# FPGA_USB.net
KiCad netlist of a schematic drawn in Altium Designer
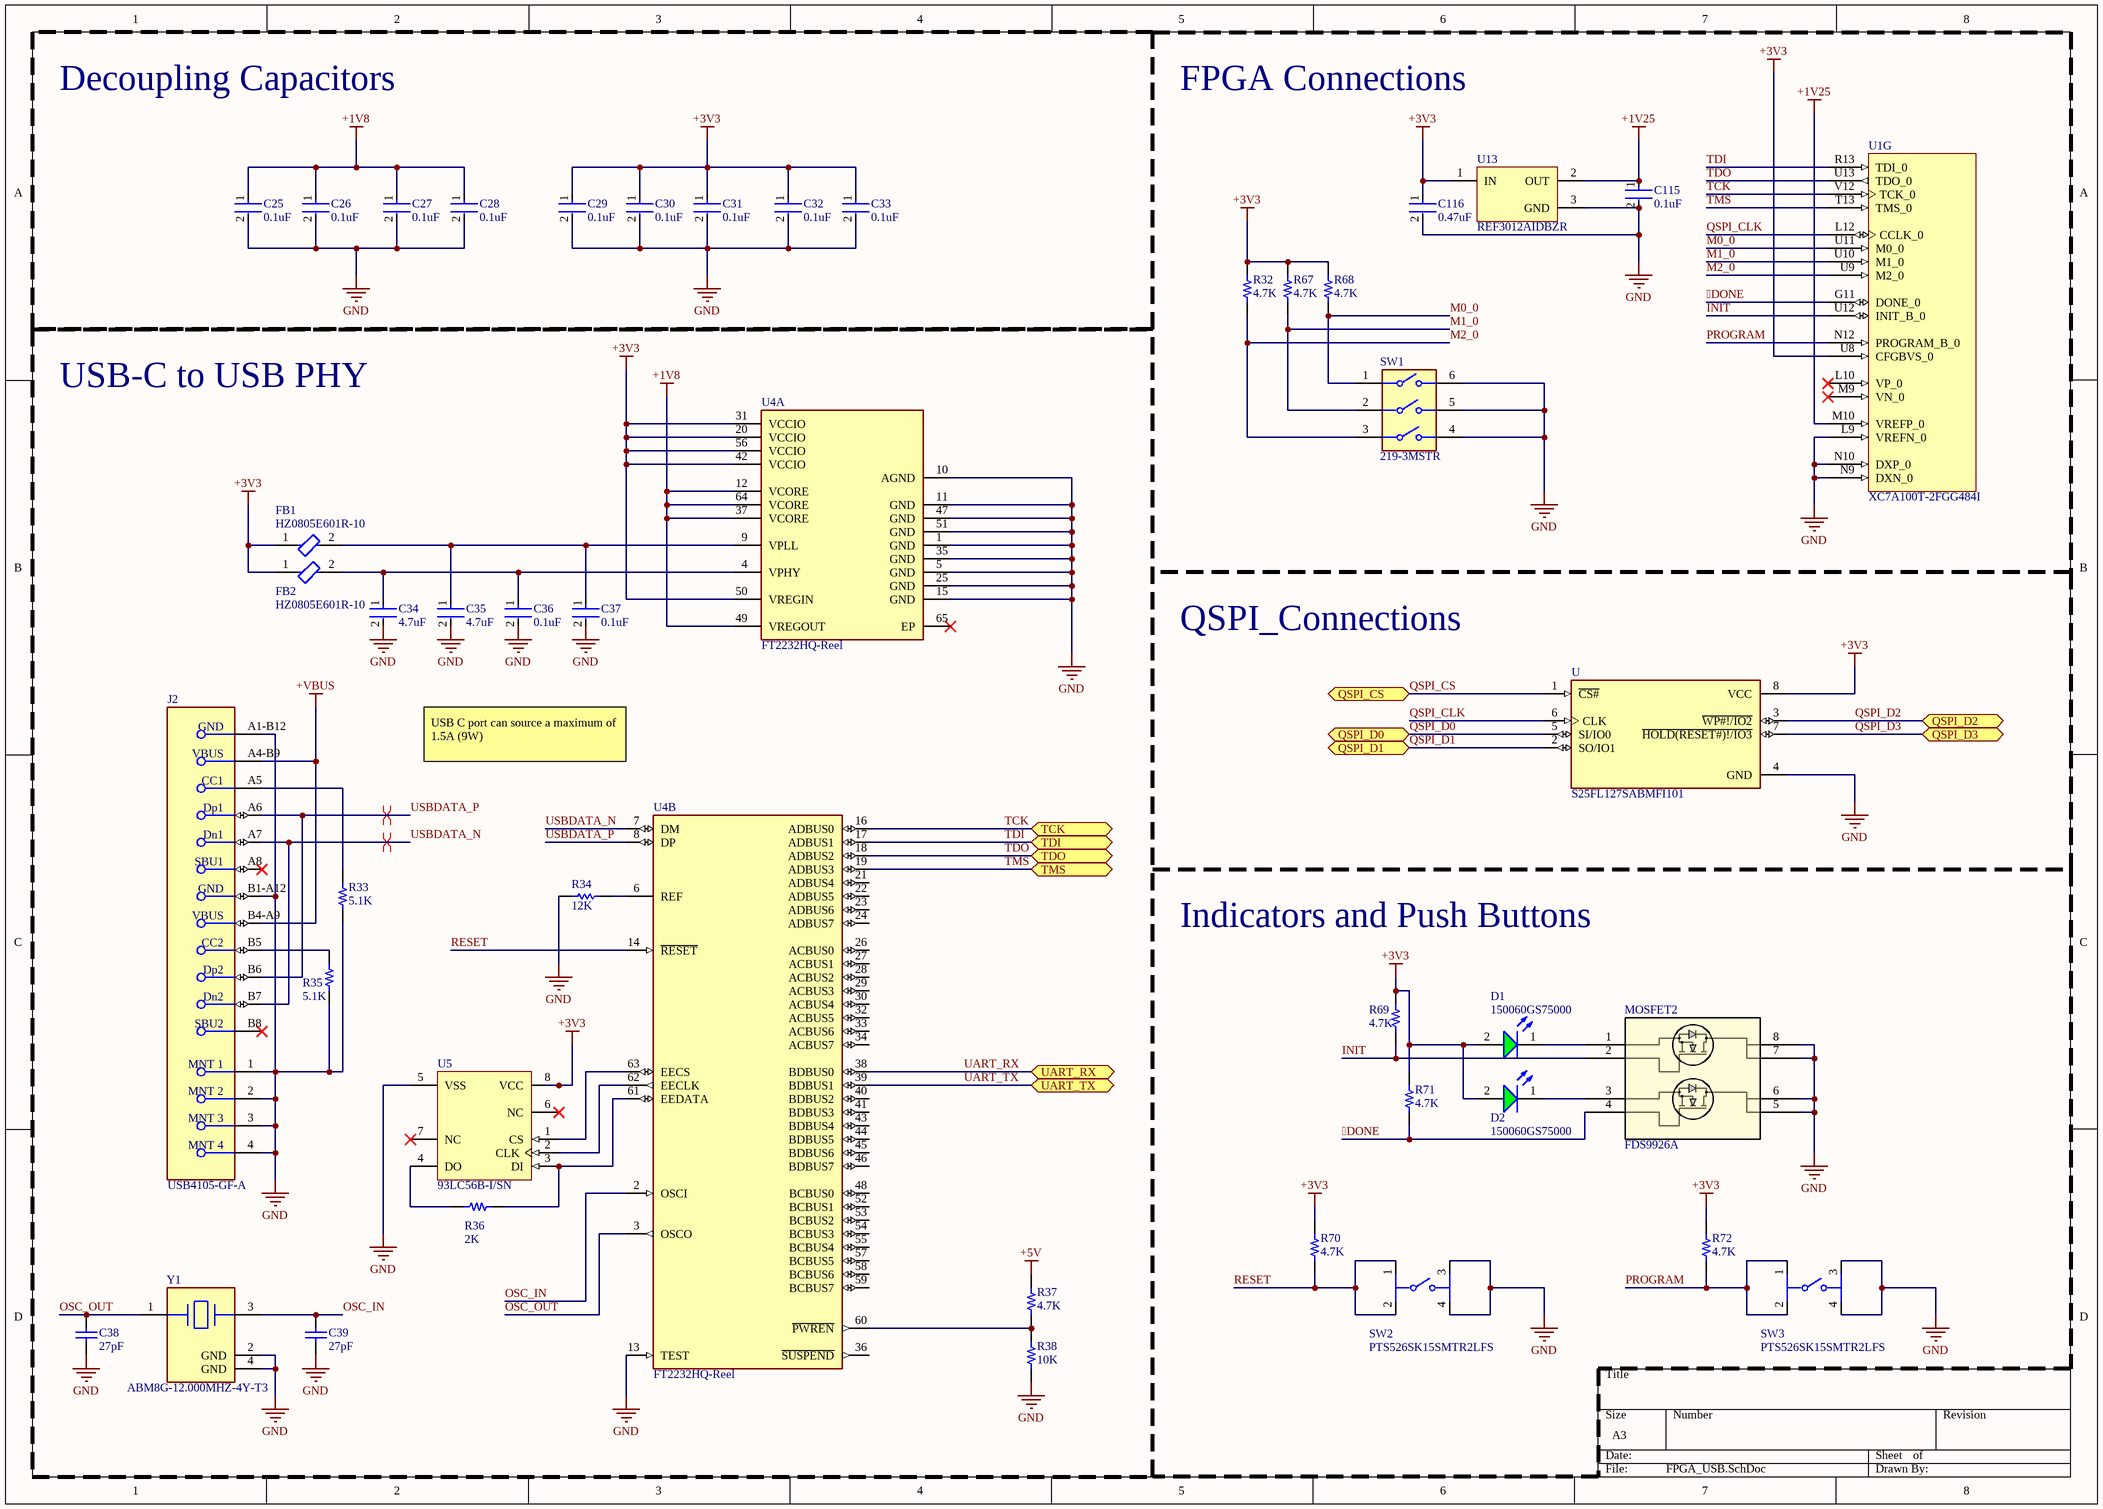
[diagram p0: FPGA_USB.SchDoc]

(export (version "E")
  (design (tool "Eeschema 10.0.6"))
  (components
    (comp (ref "C25")
      (value "0.1uF")
      (footprint "FP-CC0402-MFG")
      (description "CAP CER 0.1UF 16V X7R 0402")
      (fields (field (name "MANUFACTURER") "YAGEO") (field (name "TOLERANCE") "0.1"))
      (libsource (lib "Altium Content Vault") (part "11868f565c42a9108669ba33697ecf6"))
    )
    (comp (ref "C26")
      (value "0.1uF")
      (footprint "FP-CC0402-MFG")
      (description "CAP CER 0.1UF 16V X7R 0402")
      (fields (field (name "MANUFACTURER") "YAGEO") (field (name "TOLERANCE") "0.1"))
      (libsource (lib "Altium Content Vault") (part "11868f565c42a9108669ba33697ecf6"))
    )
    (comp (ref "C27")
      (value "0.1uF")
      (footprint "FP-CC0402-MFG")
      (description "CAP CER 0.1UF 16V X7R 0402")
      (fields (field (name "MANUFACTURER") "YAGEO") (field (name "TOLERANCE") "0.1"))
      (libsource (lib "Altium Content Vault") (part "11868f565c42a9108669ba33697ecf6"))
    )
    (comp (ref "C28")
      (value "0.1uF")
      (footprint "FP-CC0402-MFG")
      (description "CAP CER 0.1UF 16V X7R 0402")
      (fields (field (name "MANUFACTURER") "YAGEO") (field (name "TOLERANCE") "0.1"))
      (libsource (lib "Altium Content Vault") (part "11868f565c42a9108669ba33697ecf6"))
    )
    (comp (ref "C29")
      (value "0.1uF")
      (footprint "FP-CC0402-MFG")
      (description "CAP CER 0.1UF 16V X7R 0402")
      (fields (field (name "MANUFACTURER") "YAGEO") (field (name "TOLERANCE") "0.1"))
      (libsource (lib "Altium Content Vault") (part "11868f565c42a9108669ba33697ecf6"))
    )
    (comp (ref "C30")
      (value "0.1uF")
      (footprint "FP-CC0402-MFG")
      (description "CAP CER 0.1UF 16V X7R 0402")
      (fields (field (name "MANUFACTURER") "YAGEO") (field (name "TOLERANCE") "0.1"))
      (libsource (lib "Altium Content Vault") (part "11868f565c42a9108669ba33697ecf6"))
    )
    (comp (ref "C31")
      (value "0.1uF")
      (footprint "FP-CC0402-MFG")
      (description "CAP CER 0.1UF 16V X7R 0402")
      (fields (field (name "MANUFACTURER") "YAGEO") (field (name "TOLERANCE") "0.1"))
      (libsource (lib "Altium Content Vault") (part "11868f565c42a9108669ba33697ecf6"))
    )
    (comp (ref "C32")
      (value "0.1uF")
      (footprint "FP-CC0402-MFG")
      (description "CAP CER 0.1UF 16V X7R 0402")
      (fields (field (name "MANUFACTURER") "YAGEO") (field (name "TOLERANCE") "0.1"))
      (libsource (lib "Altium Content Vault") (part "11868f565c42a9108669ba33697ecf6"))
    )
    (comp (ref "C33")
      (value "0.1uF")
      (footprint "FP-CC0402-MFG")
      (description "CAP CER 0.1UF 16V X7R 0402")
      (fields (field (name "MANUFACTURER") "YAGEO") (field (name "TOLERANCE") "0.1"))
      (libsource (lib "Altium Content Vault") (part "11868f565c42a9108669ba33697ecf6"))
    )
    (comp (ref "C34")
      (value "4.7uF")
      (footprint "FP-CC0402-MFG")
      (description "CAP CER 4.7UF 10V X5R 0402")
      (fields
        (field (name "MANUFACTURER PART NUMBER") "CC0402MRX5R6BB475")
        (field (name "OCTOPART") "https://octopart.com/cc0402mrx5r6bb475-yageo-57080755")
      )
      (libsource (lib "Altium Content Vault") (part "11868f565c42a9108669ba33697ecf6"))
    )
    (comp (ref "C35")
      (value "4.7uF")
      (footprint "FP-CC0402-MFG")
      (description "CAP CER 4.7UF 10V X5R 0402")
      (fields
        (field (name "MANUFACTURER PART NUMBER") "CC0402MRX5R6BB475")
        (field (name "OCTOPART") "https://octopart.com/cc0402mrx5r6bb475-yageo-57080755")
      )
      (libsource (lib "Altium Content Vault") (part "11868f565c42a9108669ba33697ecf6"))
    )
    (comp (ref "C36")
      (value "0.1uF")
      (footprint "FP-CC0402-MFG")
      (description "CAP CER 0.1UF 16V X7R 0402")
      (fields (field (name "MANUFACTURER") "YAGEO") (field (name "TOLERANCE") "0.1"))
      (libsource (lib "Altium Content Vault") (part "11868f565c42a9108669ba33697ecf6"))
    )
    (comp (ref "C37")
      (value "0.1uF")
      (footprint "FP-CC0402-MFG")
      (description "CAP CER 0.1UF 16V X7R 0402")
      (fields (field (name "MANUFACTURER") "YAGEO") (field (name "TOLERANCE") "0.1"))
      (libsource (lib "Altium Content Vault") (part "11868f565c42a9108669ba33697ecf6"))
    )
    (comp (ref "C38")
      (value "27pF")
      (footprint "CAPC1005X55X25LL05T10")
      (fields (field (name "PART NUMBER") "GRM1555C1H270JA01D") (field (name "MANUFACTURER") "Murata"))
      (libsource (lib "Altium Content Vault") (part "CAP"))
    )
    (comp (ref "C39")
      (value "27pF")
      (footprint "CAPC1005X55X25LL05T10")
      (fields (field (name "PART NUMBER") "GRM1555C1H270JA01D") (field (name "MANUFACTURER") "Murata"))
      (libsource (lib "Altium Content Vault") (part "CAP"))
    )
    (comp (ref "C115")
      (value "0.1uF")
      (footprint "FP-CC0402-MFG")
      (description "CAP CER 0.1UF 16V X7R 0402")
      (fields (field (name "MANUFACTURER") "YAGEO") (field (name "TOLERANCE") "0.1"))
      (libsource (lib "Altium Content Vault") (part "11868f565c42a9108669ba33697ecf6"))
    )
    (comp (ref "C116")
      (value "0.47uF")
      (footprint "FP-GRM188-0_1-e0_2_0_5-MFG")
      (description "Chip Multilayer Ceramic Capacitors for General Purpose, 0603, 0.47uF, X7R, 15%, 10%, 25V")
      (fields (field (name "TOLERANCE") "10%") (field (name "VOLTAGE") "50V"))
      (libsource (lib "Altium Content Vault") (part "11868f565c42a9108669ba33697ecf6"))
    )
    (comp (ref "D1")
      (value "150060GS75000")
      (footprint "WL-SMCW_0603_150060xx75000")
      (libsource (lib "Altium Content Vault") (part "LED_Green_2A-1K"))
    )
    (comp (ref "D2")
      (value "150060GS75000")
      (footprint "WL-SMCW_0603_150060xx75000")
      (libsource (lib "Altium Content Vault") (part "LED_Green_2A-1K"))
    )
    (comp (ref "FB1")
      (value "HZ0805E601R-10")
      (footprint "FP-HZ0805-MFG")
      (description "FERRITE BEAD 600 OHM 0805 1LN")
      (libsource (lib "Altium Content Vault") (part "5f30dd21d616792df468990f7003faa"))
    )
    (comp (ref "FB2")
      (value "HZ0805E601R-10")
      (footprint "FP-HZ0805-MFG")
      (description "FERRITE BEAD 600 OHM 0805 1LN")
      (libsource (lib "Altium Content Vault") (part "5f30dd21d616792df468990f7003faa"))
    )
    (comp (ref "J2")
      (value "USB4105-GF-A")
      (footprint "FP-USB4105-GF-A-MFG")
      (description "CONN RCPT USB2.0 TYPEC 5A")
      (fields
        (field (name "MANUFACTURER") "GCT")
        (field (name "OCTOPART") "https://octopart.com/usb4105-gf-a-gct-106627878")
      )
      (libsource (lib "Altium Content Vault") (part "e7c17a616881a82b79941196b4bec10"))
    )
    (comp (ref "MOSFET2")
      (value "FDS9926A")
      (footprint "SOIC8_751EB_ONS-M")
      (description "No Description Available")
      (libsource (lib "BIG_FPGA") (part "FDS9926A"))
    )
    (comp (ref "R32")
      (value "4.7K")
      (footprint "RES 0603_1608")
      (libsource (lib "Midnight Sun") (part "Resistor"))
    )
    (comp (ref "R33")
      (value "5.1K")
      (footprint "RES 0603_1608")
      (description "5.1 kOhms ±1% 0.1W, 1/10W Chip Resistor 0603 (1608 Metric) Automotive AEC-Q200 Thick Film")
      (libsource (lib "Midnight Sun") (part "Resistor"))
    )
    (comp (ref "R34")
      (value "12K")
      (footprint "RESC1608X55X25NL10T15")
      (description "Chip Resistor, 12 KOhm, +/- 1%, 100 mW, -55 to 155 degC, 0603 (1608 Metric), RoHS, Tape and Reel")
      (fields (field (name "TOLERANCE") "1%"))
      (libsource (lib "Altium Content Vault") (part "RES-2"))
    )
    (comp (ref "R35")
      (value "5.1K")
      (footprint "RES 0603_1608")
      (description "5.1 kOhms ±1% 0.1W, 1/10W Chip Resistor 0603 (1608 Metric) Automotive AEC-Q200 Thick Film")
      (libsource (lib "Midnight Sun") (part "Resistor"))
    )
    (comp (ref "R36")
      (value "2K")
      (footprint "RES 0603_1608")
      (description "2k Ohm ±1% 0.1W, 1/10W Chip Resistor 0603 (1608 Metric) Moisture Resistant Thick Film")
      (libsource (lib "Midnight Sun") (part "Resistor"))
    )
    (comp (ref "R37")
      (value "4.7K")
      (footprint "RES 0603_1608")
      (libsource (lib "Midnight Sun") (part "Resistor"))
    )
    (comp (ref "R38")
      (value "10K")
      (footprint "RES 0603_1608")
      (description "10 ±1% 0.1W, 1/10W Chip Resistor 0603 (1608 Metric) Automotive AEC-Q200 Thick Film")
      (libsource (lib "Midnight Sun") (part "Resistor"))
    )
    (comp (ref "R67")
      (value "4.7K")
      (footprint "RES 0603_1608")
      (libsource (lib "Midnight Sun") (part "Resistor"))
    )
    (comp (ref "R68")
      (value "4.7K")
      (footprint "RES 0603_1608")
      (libsource (lib "Midnight Sun") (part "Resistor"))
    )
    (comp (ref "R69")
      (value "4.7K")
      (footprint "RES 0603_1608")
      (libsource (lib "Midnight Sun") (part "Resistor"))
    )
    (comp (ref "R70")
      (value "4.7K")
      (footprint "RES 0603_1608")
      (libsource (lib "Midnight Sun") (part "Resistor"))
    )
    (comp (ref "R71")
      (value "4.7K")
      (footprint "RES 0603_1608")
      (libsource (lib "Midnight Sun") (part "Resistor"))
    )
    (comp (ref "R72")
      (value "4.7K")
      (footprint "RES 0603_1608")
      (libsource (lib "Midnight Sun") (part "Resistor"))
    )
    (comp (ref "SW1")
      (value "219-3MSTR")
      (footprint "FP-219-3MSTR-MFG")
      (description "SWITCH SLIDE DIP SPST 100MA 20V")
      (libsource (lib "Altium Content Vault") (part "7c490946f25aa2bb1cd4cef5bc3ec4e"))
    )
    (comp (ref "SW2")
      (value "PTS526SK15SMTR2LFS")
      (footprint "FP-PTS526SK15SMTR2LFS-MFG")
      (description "TACT 5.2 X 5.2, 1.5 MM H, 260GF,")
      (fields
        (field (name "MANUFACTURER") "C&K")
        (field (name "OCTOPART") "https://octopart.com/pts526+sk15+smtr2+lfs-c%26k+components-100617999")
      )
      (libsource (lib "Altium Content Vault") (part "b8895f3f4cefb76e1819d2863dba89b"))
    )
    (comp (ref "SW3")
      (value "PTS526SK15SMTR2LFS")
      (footprint "FP-PTS526SK15SMTR2LFS-MFG")
      (description "TACT 5.2 X 5.2, 1.5 MM H, 260GF,")
      (fields
        (field (name "MANUFACTURER") "C&K")
        (field (name "OCTOPART") "https://octopart.com/pts526+sk15+smtr2+lfs-c%26k+components-100617999")
      )
      (libsource (lib "Altium Content Vault") (part "b8895f3f4cefb76e1819d2863dba89b"))
    )
    (comp (ref "U")
      (value "S25FL127SABMFI101")
      (footprint "SOIC127P800X216-8N")
      (description "FLASH - NOR Memory IC 128Mb _16M x 8_ SPI - Quad I/O 108MHz 8-SOIC")
      (fields
        (field (name "MF") "Cypress Semiconductor")
        (field (name "DIGI-KEY_PART_NUMBER") "1274-1045-ND")
      )
      (libsource (lib "BIG_FPGA") (part "S25FL127SABMFI101"))
    )
    (comp (ref "U1")
      (value "XC7A100T-2FGG484I")
      (footprint "FGG484")
      (description "Artix-7 FPGA, 285 User I/Os, 4 GTP, 484-Ball BGA, Speed Grade 2, Industrial Grade, Pb-Free")
      (fields (field (name "MANUFACTURER") "Xilinx") (field (name "GENERIC PART NUMBER") "XC7A100T"))
      (libsource (lib "Altium Content Vault") (part "XNLX-XC7A100T-XNLX-FGG484"))
    )
    (comp (ref "U4")
      (value "FT2232HQ-Reel")
      (footprint "FP-FT2232HQ-Reel-MFG")
      (description "USB Bridge, USB to UART,FIFO USB 2.0 UART Interface 64-QFN (9x9)")
      (fields (field (name "OCTOPART") "https://octopart.com/ft2232hq-reel-ftdi-19172126"))
      (libsource (lib "Altium Content Vault") (part "69ab9ac86b67af101dfdf5de5064102"))
    )
    (comp (ref "U5")
      (value "93LC56B-I/SN")
      (footprint "SOIC-SN8_L")
      (description "2K, 128x16-bit, 2.5V Microwire Serial EEPROM, 8-Pin SOIC 150mil, Industrial Temperature")
      (libsource (lib "Altium Content Vault") (part "MEM-SEEPROM-93AA46B-P-8"))
    )
    (comp (ref "U13")
      (value "REF3012AIDBZR")
      (footprint "DBZ0003A_M")
      (fields (field (name "MANUFACTURER") "Texas Instruments"))
      (libsource (lib "Altium Content Vault") (part "TI-REF3012DBZ3"))
    )
    (comp (ref "Y1")
      (value "ABM8G-12.000MHZ-4Y-T3")
      (footprint "FP-ABM8G-MFG")
      (description "Crystal 12MHz ±30ppm (Tol) ±30ppm (Stability) 10pF FUND 120Ω 4-Pin SMD T/R")
      (libsource (lib "Altium Content Vault") (part "48e526d86b7f2615d98721063c72f49"))
    )
  )
  (nets
    (net (code "1") (name "+1V8") (class "Default")
      (node (ref "C25") (pin "1") (pinfunction "1_1") (pintype "passive"))
      (node (ref "C26") (pin "1") (pinfunction "1_1") (pintype "passive"))
      (node (ref "C27") (pin "1") (pinfunction "1_1") (pintype "passive"))
      (node (ref "C28") (pin "1") (pinfunction "1_1") (pintype "passive"))
      (node (ref "U4") (pin "12") (pinfunction "VCORE_12") (pintype "power_in"))
      (node (ref "U4") (pin "37") (pinfunction "VCORE_37") (pintype "power_in"))
      (node (ref "U4") (pin "49") (pinfunction "VREGOUT_49") (pintype "power_in"))
      (node (ref "U4") (pin "64") (pinfunction "VCORE_64") (pintype "power_in"))
    )
    (net (code "2") (name "+1V25") (class "Default")
      (node (ref "C115") (pin "1") (pinfunction "1_1") (pintype "passive"))
      (node (ref "U1") (pin "M10") (pinfunction "VREFP_0_M10") (pintype "input"))
      (node (ref "U13") (pin "2") (pinfunction "OUT_2") (pintype "power_in"))
    )
    (net (code "3") (name "+3V3") (class "Default")
      (node (ref "C116") (pin "1") (pinfunction "1_1") (pintype "passive"))
      (node (ref "C29") (pin "1") (pinfunction "1_1") (pintype "passive"))
      (node (ref "C30") (pin "1") (pinfunction "1_1") (pintype "passive"))
      (node (ref "C31") (pin "1") (pinfunction "1_1") (pintype "passive"))
      (node (ref "C32") (pin "1") (pinfunction "1_1") (pintype "passive"))
      (node (ref "C33") (pin "1") (pinfunction "1_1") (pintype "passive"))
      (node (ref "D1") (pin "2") (pinfunction "A_2") (pintype "passive"))
      (node (ref "D2") (pin "2") (pinfunction "A_2") (pintype "passive"))
      (node (ref "FB1") (pin "1") (pinfunction "1_1") (pintype "passive"))
      (node (ref "FB2") (pin "1") (pinfunction "1_1") (pintype "passive"))
      (node (ref "R32") (pin "2") (pinfunction "2_2") (pintype "passive"))
      (node (ref "R67") (pin "1") (pinfunction "1_1") (pintype "passive"))
      (node (ref "R68") (pin "1") (pinfunction "1_1") (pintype "passive"))
      (node (ref "R69") (pin "1") (pinfunction "1_1") (pintype "passive"))
      (node (ref "R70") (pin "1") (pinfunction "1_1") (pintype "passive"))
      (node (ref "R71") (pin "1") (pinfunction "1_1") (pintype "passive"))
      (node (ref "R72") (pin "1") (pinfunction "1_1") (pintype "passive"))
      (node (ref "U") (pin "8") (pinfunction "VCC_8") (pintype "power_in"))
      (node (ref "U1") (pin "U8") (pinfunction "CFGBVS_0_U8") (pintype "input"))
      (node (ref "U13") (pin "1") (pinfunction "IN_1") (pintype "power_in"))
      (node (ref "U4") (pin "20") (pinfunction "VCCIO_20") (pintype "power_in"))
      (node (ref "U4") (pin "31") (pinfunction "VCCIO_31") (pintype "power_in"))
      (node (ref "U4") (pin "42") (pinfunction "VCCIO_42") (pintype "power_in"))
      (node (ref "U4") (pin "50") (pinfunction "VREGIN_50") (pintype "power_in"))
      (node (ref "U4") (pin "56") (pinfunction "VCCIO_56") (pintype "power_in"))
      (node (ref "U5") (pin "8") (pinfunction "VCC_8") (pintype "power_in"))
    )
    (net (code "4") (name "+5V") (class "Default")
      (node (ref "R37") (pin "1") (pinfunction "1_1") (pintype "passive"))
    )
    (net (code "5") (name "+VBUS") (class "Default")
      (node (ref "J2") (pin "A4-B9") (pinfunction "VBUS_A4-B9") (pintype "power_in"))
      (node (ref "J2") (pin "B4-A9") (pinfunction "VBUS_B4-A9") (pintype "bidirectional"))
    )
    (net (code "6") (name "/DONE") (class "Default")
      (node (ref "MOSFET2") (pin "4") (pinfunction "4_4") (pintype "passive"))
      (node (ref "R71") (pin "2") (pinfunction "2_2") (pintype "passive"))
      (node (ref "U1") (pin "G11") (pinfunction "DONE_0_G11") (pintype "bidirectional"))
    )
    (net (code "7") (name "/INIT") (class "Default")
      (node (ref "MOSFET2") (pin "2") (pinfunction "2_2") (pintype "passive"))
      (node (ref "R69") (pin "2") (pinfunction "2_2") (pintype "passive"))
      (node (ref "U1") (pin "U12") (pinfunction "INIT_B_0_U12") (pintype "bidirectional"))
    )
    (net (code "8") (name "/M0_0") (class "Default")
      (node (ref "R68") (pin "2") (pinfunction "2_2") (pintype "passive"))
      (node (ref "SW1") (pin "1") (pinfunction "1_1") (pintype "passive"))
      (node (ref "U1") (pin "U11") (pinfunction "M0_0_U11") (pintype "input"))
    )
    (net (code "9") (name "/M1_0") (class "Default")
      (node (ref "R67") (pin "2") (pinfunction "2_2") (pintype "passive"))
      (node (ref "SW1") (pin "2") (pinfunction "2_2") (pintype "passive"))
      (node (ref "U1") (pin "U10") (pinfunction "M1_0_U10") (pintype "input"))
    )
    (net (code "10") (name "/M2_0") (class "Default")
      (node (ref "R32") (pin "1") (pinfunction "1_1") (pintype "passive"))
      (node (ref "SW1") (pin "3") (pinfunction "3_3") (pintype "passive"))
      (node (ref "U1") (pin "U9") (pinfunction "M2_0_U9") (pintype "input"))
    )
    (net (code "11") (name "/OSC_IN") (class "Default")
      (node (ref "C39") (pin "1") (pinfunction "1_1") (pintype "passive"))
      (node (ref "U4") (pin "2") (pinfunction "OSCI_2") (pintype "input"))
      (node (ref "Y1") (pin "3") (pinfunction "3_3") (pintype "passive"))
    )
    (net (code "12") (name "/OSC_OUT") (class "Default")
      (node (ref "C38") (pin "1") (pinfunction "1_1") (pintype "passive"))
      (node (ref "U4") (pin "3") (pinfunction "OSCO_3") (pintype "output"))
      (node (ref "Y1") (pin "1") (pinfunction "1_1") (pintype "passive"))
    )
    (net (code "13") (name "/PROGRAM") (class "Default")
      (node (ref "R72") (pin "2") (pinfunction "2_2") (pintype "passive"))
      (node (ref "SW3") (pin "1") (pinfunction "1_1") (pintype "passive"))
      (node (ref "SW3") (pin "2") (pinfunction "2_2") (pintype "passive"))
      (node (ref "U1") (pin "N12") (pinfunction "PROGRAM_B_0_N12") (pintype "input"))
    )
    (net (code "14") (name "/QSPI_CLK") (class "Default")
      (node (ref "U") (pin "6") (pinfunction "CLK_6") (pintype "input"))
      (node (ref "U1") (pin "L12") (pinfunction "CCLK_0_L12") (pintype "bidirectional"))
    )
    (net (code "15") (name "/QSPI_CS") (class "Default")
      (node (ref "U") (pin "1") (pinfunction "~{CS#}_1") (pintype "input"))
    )
    (net (code "16") (name "/QSPI_D0") (class "Default")
      (node (ref "U") (pin "5") (pinfunction "SI/IO0_5") (pintype "bidirectional"))
    )
    (net (code "17") (name "/QSPI_D1") (class "Default")
      (node (ref "U") (pin "2") (pinfunction "SO/IO1_2") (pintype "bidirectional"))
    )
    (net (code "18") (name "/QSPI_D2") (class "Default")
      (node (ref "U") (pin "3") (pinfunction "~{WP#!/IO2}_3") (pintype "bidirectional"))
    )
    (net (code "19") (name "/QSPI_D3") (class "Default")
      (node (ref "U") (pin "7") (pinfunction "~{HOLD(RESET#)!/IO3}_7") (pintype "bidirectional"))
    )
    (net (code "20") (name "/RESET") (class "Default")
      (node (ref "R70") (pin "2") (pinfunction "2_2") (pintype "passive"))
      (node (ref "SW2") (pin "1") (pinfunction "1_1") (pintype "passive"))
      (node (ref "SW2") (pin "2") (pinfunction "2_2") (pintype "passive"))
      (node (ref "U4") (pin "14") (pinfunction "~{RESET}_14") (pintype "input"))
    )
    (net (code "21") (name "/TCK") (class "Default")
      (node (ref "U1") (pin "V12") (pinfunction "TCK_0_V12") (pintype "input"))
      (node (ref "U4") (pin "16") (pinfunction "ADBUS0_16") (pintype "bidirectional"))
    )
    (net (code "22") (name "/TDI") (class "Default")
      (node (ref "U1") (pin "R13") (pinfunction "TDI_0_R13") (pintype "input"))
      (node (ref "U4") (pin "17") (pinfunction "ADBUS1_17") (pintype "bidirectional"))
    )
    (net (code "23") (name "/TDO") (class "Default")
      (node (ref "U1") (pin "U13") (pinfunction "TDO_0_U13") (pintype "output"))
      (node (ref "U4") (pin "18") (pinfunction "ADBUS2_18") (pintype "bidirectional"))
    )
    (net (code "24") (name "/TMS") (class "Default")
      (node (ref "U1") (pin "T13") (pinfunction "TMS_0_T13") (pintype "input"))
      (node (ref "U4") (pin "19") (pinfunction "ADBUS3_19") (pintype "bidirectional"))
    )
    (net (code "25") (name "/UART_RX") (class "Default")
      (node (ref "U4") (pin "38") (pinfunction "BDBUS0_38") (pintype "bidirectional"))
    )
    (net (code "26") (name "/UART_TX") (class "Default")
      (node (ref "U4") (pin "39") (pinfunction "BDBUS1_39") (pintype "bidirectional"))
    )
    (net (code "27") (name "/USBDATA_N") (class "Default")
      (node (ref "J2") (pin "A7") (pinfunction "Dn1_A7") (pintype "bidirectional"))
      (node (ref "J2") (pin "B7") (pinfunction "Dn2_B7") (pintype "bidirectional"))
      (node (ref "U4") (pin "7") (pinfunction "DM_7") (pintype "bidirectional"))
    )
    (net (code "28") (name "/USBDATA_P") (class "Default")
      (node (ref "J2") (pin "A6") (pinfunction "Dp1_A6") (pintype "bidirectional"))
      (node (ref "J2") (pin "B6") (pinfunction "Dp2_B6") (pintype "bidirectional"))
      (node (ref "U4") (pin "8") (pinfunction "DP_8") (pintype "bidirectional"))
    )
    (net (code "29") (name "GND") (class "Default")
      (node (ref "C115") (pin "2") (pinfunction "2_2") (pintype "passive"))
      (node (ref "C116") (pin "2") (pinfunction "2_2") (pintype "passive"))
      (node (ref "C25") (pin "2") (pinfunction "2_2") (pintype "passive"))
      (node (ref "C26") (pin "2") (pinfunction "2_2") (pintype "passive"))
      (node (ref "C27") (pin "2") (pinfunction "2_2") (pintype "passive"))
      (node (ref "C28") (pin "2") (pinfunction "2_2") (pintype "passive"))
      (node (ref "C29") (pin "2") (pinfunction "2_2") (pintype "passive"))
      (node (ref "C30") (pin "2") (pinfunction "2_2") (pintype "passive"))
      (node (ref "C31") (pin "2") (pinfunction "2_2") (pintype "passive"))
      (node (ref "C32") (pin "2") (pinfunction "2_2") (pintype "passive"))
      (node (ref "C33") (pin "2") (pinfunction "2_2") (pintype "passive"))
      (node (ref "C34") (pin "2") (pinfunction "2_2") (pintype "passive"))
      (node (ref "C35") (pin "2") (pinfunction "2_2") (pintype "passive"))
      (node (ref "C36") (pin "2") (pinfunction "2_2") (pintype "passive"))
      (node (ref "C37") (pin "2") (pinfunction "2_2") (pintype "passive"))
      (node (ref "C38") (pin "2") (pinfunction "2_2") (pintype "passive"))
      (node (ref "C39") (pin "2") (pinfunction "2_2") (pintype "passive"))
      (node (ref "J2") (pin "1") (pinfunction "MNT_1_1") (pintype "power_in"))
      (node (ref "J2") (pin "2") (pinfunction "MNT_2_2") (pintype "power_in"))
      (node (ref "J2") (pin "3") (pinfunction "MNT_3_3") (pintype "power_in"))
      (node (ref "J2") (pin "4") (pinfunction "MNT_4_4") (pintype "power_in"))
      (node (ref "J2") (pin "A1-B12") (pinfunction "GND_A1-B12") (pintype "power_in"))
      (node (ref "J2") (pin "B1-A12") (pinfunction "GND_B1-A12") (pintype "bidirectional"))
      (node (ref "MOSFET2") (pin "5") (pinfunction "5_5") (pintype "passive"))
      (node (ref "MOSFET2") (pin "6") (pinfunction "6_6") (pintype "passive"))
      (node (ref "MOSFET2") (pin "7") (pinfunction "7_7") (pintype "passive"))
      (node (ref "MOSFET2") (pin "8") (pinfunction "8_8") (pintype "passive"))
      (node (ref "R33") (pin "2") (pinfunction "2_2") (pintype "passive"))
      (node (ref "R34") (pin "1") (pinfunction "1_1") (pintype "passive"))
      (node (ref "R35") (pin "2") (pinfunction "2_2") (pintype "passive"))
      (node (ref "R38") (pin "2") (pinfunction "2_2") (pintype "passive"))
      (node (ref "SW1") (pin "4") (pinfunction "4_4") (pintype "passive"))
      (node (ref "SW1") (pin "5") (pinfunction "5_5") (pintype "passive"))
      (node (ref "SW1") (pin "6") (pinfunction "6_6") (pintype "passive"))
      (node (ref "SW2") (pin "3") (pinfunction "3_3") (pintype "passive"))
      (node (ref "SW2") (pin "4") (pinfunction "4_4") (pintype "passive"))
      (node (ref "SW3") (pin "3") (pinfunction "3_3") (pintype "passive"))
      (node (ref "SW3") (pin "4") (pinfunction "4_4") (pintype "passive"))
      (node (ref "U") (pin "4") (pinfunction "GND_4") (pintype "power_in"))
      (node (ref "U1") (pin "L9") (pinfunction "VREFN_0_L9") (pintype "input"))
      (node (ref "U1") (pin "N10") (pinfunction "DXP_0_N10") (pintype "input"))
      (node (ref "U1") (pin "N9") (pinfunction "DXN_0_N9") (pintype "input"))
      (node (ref "U13") (pin "3") (pinfunction "GND_3") (pintype "power_in"))
      (node (ref "U4") (pin "1") (pinfunction "GND_1") (pintype "power_in"))
      (node (ref "U4") (pin "10") (pinfunction "AGND_10") (pintype "power_in"))
      (node (ref "U4") (pin "11") (pinfunction "GND_11") (pintype "power_in"))
      (node (ref "U4") (pin "13") (pinfunction "TEST_13") (pintype "input"))
      (node (ref "U4") (pin "15") (pinfunction "GND_15") (pintype "power_in"))
      (node (ref "U4") (pin "25") (pinfunction "GND_25") (pintype "power_in"))
      (node (ref "U4") (pin "35") (pinfunction "GND_35") (pintype "power_in"))
      (node (ref "U4") (pin "47") (pinfunction "GND_47") (pintype "power_in"))
      (node (ref "U4") (pin "5") (pinfunction "GND_5") (pintype "power_in"))
      (node (ref "U4") (pin "51") (pinfunction "GND_51") (pintype "power_in"))
      (node (ref "U5") (pin "5") (pinfunction "VSS_5") (pintype "power_in"))
      (node (ref "Y1") (pin "2") (pinfunction "GND_2") (pintype "power_in"))
      (node (ref "Y1") (pin "4") (pinfunction "GND_4") (pintype "power_in"))
    )
    (net (code "30") (name "Net-(D1-K)") (class "Default")
      (node (ref "D1") (pin "1") (pinfunction "K_1") (pintype "passive"))
      (node (ref "MOSFET2") (pin "1") (pinfunction "1_1") (pintype "passive"))
    )
    (net (code "31") (name "Net-(D2-K)") (class "Default")
      (node (ref "D2") (pin "1") (pinfunction "K_1") (pintype "passive"))
      (node (ref "MOSFET2") (pin "3") (pinfunction "3_3") (pintype "passive"))
    )
    (net (code "32") (name "Net-(J2-CC1)") (class "Default")
      (node (ref "J2") (pin "A5") (pinfunction "CC1_A5") (pintype "power_in"))
      (node (ref "R33") (pin "1") (pinfunction "1_1") (pintype "passive"))
    )
    (net (code "33") (name "Net-(J2-CC2)") (class "Default")
      (node (ref "J2") (pin "B5") (pinfunction "CC2_B5") (pintype "bidirectional"))
      (node (ref "R35") (pin "1") (pinfunction "1_1") (pintype "passive"))
    )
    (net (code "34") (name "Net-(U4A-VPHY)") (class "Default")
      (node (ref "C34") (pin "1") (pinfunction "1_1") (pintype "passive"))
      (node (ref "C36") (pin "1") (pinfunction "1_1") (pintype "passive"))
      (node (ref "FB2") (pin "2") (pinfunction "2_2") (pintype "passive"))
      (node (ref "U4") (pin "4") (pinfunction "VPHY_4") (pintype "power_in"))
    )
    (net (code "35") (name "Net-(U4A-VPLL)") (class "Default")
      (node (ref "C35") (pin "1") (pinfunction "1_1") (pintype "passive"))
      (node (ref "C37") (pin "1") (pinfunction "1_1") (pintype "passive"))
      (node (ref "FB1") (pin "2") (pinfunction "2_2") (pintype "passive"))
      (node (ref "U4") (pin "9") (pinfunction "VPLL_9") (pintype "power_in"))
    )
    (net (code "36") (name "Net-(U4B-EECLK)") (class "Default")
      (node (ref "U4") (pin "62") (pinfunction "EECLK_62") (pintype "output"))
      (node (ref "U5") (pin "2") (pinfunction "CLK_2") (pintype "input"))
    )
    (net (code "37") (name "Net-(U4B-EECS)") (class "Default")
      (node (ref "U4") (pin "63") (pinfunction "EECS_63") (pintype "bidirectional"))
      (node (ref "U5") (pin "1") (pinfunction "CS_1") (pintype "input"))
    )
    (net (code "38") (name "Net-(U4B-EEDATA)") (class "Default")
      (node (ref "R36") (pin "2") (pinfunction "2_2") (pintype "passive"))
      (node (ref "U4") (pin "61") (pinfunction "EEDATA_61") (pintype "bidirectional"))
      (node (ref "U5") (pin "3") (pinfunction "DI_3") (pintype "input"))
    )
    (net (code "39") (name "Net-(U4B-REF)") (class "Default")
      (node (ref "R34") (pin "2") (pinfunction "2_2") (pintype "passive"))
      (node (ref "U4") (pin "6") (pinfunction "REF_6") (pintype "passive"))
    )
    (net (code "40") (name "Net-(U4B-~{PWREN})") (class "Default")
      (node (ref "R37") (pin "2") (pinfunction "2_2") (pintype "passive"))
      (node (ref "R38") (pin "1") (pinfunction "1_1") (pintype "passive"))
      (node (ref "U4") (pin "60") (pinfunction "~{PWREN}_60") (pintype "output"))
    )
    (net (code "41") (name "Net-(U5-DO)") (class "Default")
      (node (ref "R36") (pin "1") (pinfunction "1_1") (pintype "passive"))
      (node (ref "U5") (pin "4") (pinfunction "DO_4") (pintype "tri_state"))
    )
    (net (code "42") (name "unconnected-(J2-SBU1-PadA8)") (class "Default")
      (node (ref "J2") (pin "A8") (pinfunction "SBU1_A8") (pintype "bidirectional+no_connect"))
    )
    (net (code "43") (name "unconnected-(J2-SBU2-PadB8)") (class "Default")
      (node (ref "J2") (pin "B8") (pinfunction "SBU2_B8") (pintype "power_in+no_connect"))
    )
    (net (code "44") (name "unconnected-(U1G-VN_0-PadM9)") (class "Default")
      (node (ref "U1") (pin "M9") (pinfunction "VN_0_M9") (pintype "input+no_connect"))
    )
    (net (code "45") (name "unconnected-(U1G-VP_0-PadL10)") (class "Default")
      (node (ref "U1") (pin "L10") (pinfunction "VP_0_L10") (pintype "input+no_connect"))
    )
    (net (code "46") (name "unconnected-(U4A-EP-Pad65)") (class "Default")
      (node (ref "U4") (pin "65") (pinfunction "EP_65") (pintype "passive+no_connect"))
    )
    (net (code "47") (name "unconnected-(U4B-ACBUS0-Pad26)") (class "Default")
      (node (ref "U4") (pin "26") (pinfunction "ACBUS0_26") (pintype "bidirectional"))
    )
    (net (code "48") (name "unconnected-(U4B-ACBUS1-Pad27)") (class "Default")
      (node (ref "U4") (pin "27") (pinfunction "ACBUS1_27") (pintype "bidirectional"))
    )
    (net (code "49") (name "unconnected-(U4B-ACBUS2-Pad28)") (class "Default")
      (node (ref "U4") (pin "28") (pinfunction "ACBUS2_28") (pintype "bidirectional"))
    )
    (net (code "50") (name "unconnected-(U4B-ACBUS3-Pad29)") (class "Default")
      (node (ref "U4") (pin "29") (pinfunction "ACBUS3_29") (pintype "bidirectional"))
    )
    (net (code "51") (name "unconnected-(U4B-ACBUS4-Pad30)") (class "Default")
      (node (ref "U4") (pin "30") (pinfunction "ACBUS4_30") (pintype "bidirectional"))
    )
    (net (code "52") (name "unconnected-(U4B-ACBUS5-Pad32)") (class "Default")
      (node (ref "U4") (pin "32") (pinfunction "ACBUS5_32") (pintype "bidirectional"))
    )
    (net (code "53") (name "unconnected-(U4B-ACBUS6-Pad33)") (class "Default")
      (node (ref "U4") (pin "33") (pinfunction "ACBUS6_33") (pintype "bidirectional"))
    )
    (net (code "54") (name "unconnected-(U4B-ACBUS7-Pad34)") (class "Default")
      (node (ref "U4") (pin "34") (pinfunction "ACBUS7_34") (pintype "bidirectional"))
    )
    (net (code "55") (name "unconnected-(U4B-ADBUS4-Pad21)") (class "Default")
      (node (ref "U4") (pin "21") (pinfunction "ADBUS4_21") (pintype "bidirectional"))
    )
    (net (code "56") (name "unconnected-(U4B-ADBUS5-Pad22)") (class "Default")
      (node (ref "U4") (pin "22") (pinfunction "ADBUS5_22") (pintype "bidirectional"))
    )
    (net (code "57") (name "unconnected-(U4B-ADBUS6-Pad23)") (class "Default")
      (node (ref "U4") (pin "23") (pinfunction "ADBUS6_23") (pintype "bidirectional"))
    )
    (net (code "58") (name "unconnected-(U4B-ADBUS7-Pad24)") (class "Default")
      (node (ref "U4") (pin "24") (pinfunction "ADBUS7_24") (pintype "bidirectional"))
    )
    (net (code "59") (name "unconnected-(U4B-BCBUS0-Pad48)") (class "Default")
      (node (ref "U4") (pin "48") (pinfunction "BCBUS0_48") (pintype "bidirectional"))
    )
    (net (code "60") (name "unconnected-(U4B-BCBUS1-Pad52)") (class "Default")
      (node (ref "U4") (pin "52") (pinfunction "BCBUS1_52") (pintype "bidirectional"))
    )
    (net (code "61") (name "unconnected-(U4B-BCBUS2-Pad53)") (class "Default")
      (node (ref "U4") (pin "53") (pinfunction "BCBUS2_53") (pintype "bidirectional"))
    )
    (net (code "62") (name "unconnected-(U4B-BCBUS3-Pad54)") (class "Default")
      (node (ref "U4") (pin "54") (pinfunction "BCBUS3_54") (pintype "bidirectional"))
    )
    (net (code "63") (name "unconnected-(U4B-BCBUS4-Pad55)") (class "Default")
      (node (ref "U4") (pin "55") (pinfunction "BCBUS4_55") (pintype "bidirectional"))
    )
    (net (code "64") (name "unconnected-(U4B-BCBUS5-Pad57)") (class "Default")
      (node (ref "U4") (pin "57") (pinfunction "BCBUS5_57") (pintype "bidirectional"))
    )
    (net (code "65") (name "unconnected-(U4B-BCBUS6-Pad58)") (class "Default")
      (node (ref "U4") (pin "58") (pinfunction "BCBUS6_58") (pintype "bidirectional"))
    )
    (net (code "66") (name "unconnected-(U4B-BCBUS7-Pad59)") (class "Default")
      (node (ref "U4") (pin "59") (pinfunction "BCBUS7_59") (pintype "bidirectional"))
    )
    (net (code "67") (name "unconnected-(U4B-BDBUS2-Pad40)") (class "Default")
      (node (ref "U4") (pin "40") (pinfunction "BDBUS2_40") (pintype "bidirectional"))
    )
    (net (code "68") (name "unconnected-(U4B-BDBUS3-Pad41)") (class "Default")
      (node (ref "U4") (pin "41") (pinfunction "BDBUS3_41") (pintype "bidirectional"))
    )
    (net (code "69") (name "unconnected-(U4B-BDBUS4-Pad43)") (class "Default")
      (node (ref "U4") (pin "43") (pinfunction "BDBUS4_43") (pintype "bidirectional"))
    )
    (net (code "70") (name "unconnected-(U4B-BDBUS5-Pad44)") (class "Default")
      (node (ref "U4") (pin "44") (pinfunction "BDBUS5_44") (pintype "bidirectional"))
    )
    (net (code "71") (name "unconnected-(U4B-BDBUS6-Pad45)") (class "Default")
      (node (ref "U4") (pin "45") (pinfunction "BDBUS6_45") (pintype "bidirectional"))
    )
    (net (code "72") (name "unconnected-(U4B-BDBUS7-Pad46)") (class "Default")
      (node (ref "U4") (pin "46") (pinfunction "BDBUS7_46") (pintype "bidirectional"))
    )
    (net (code "73") (name "unconnected-(U4B-~{SUSPEND}-Pad36)") (class "Default")
      (node (ref "U4") (pin "36") (pinfunction "~{SUSPEND}_36") (pintype "output"))
    )
    (net (code "74") (name "unconnected-(U5-NC-Pad6)") (class "Default")
      (node (ref "U5") (pin "6") (pinfunction "NC_6") (pintype "passive+no_connect"))
    )
    (net (code "75") (name "unconnected-(U5-NC-Pad7)") (class "Default")
      (node (ref "U5") (pin "7") (pinfunction "NC_7") (pintype "passive+no_connect"))
    )
  )
)
